# HSMC.net
KiCad netlist of a schematic drawn in Altium Designer
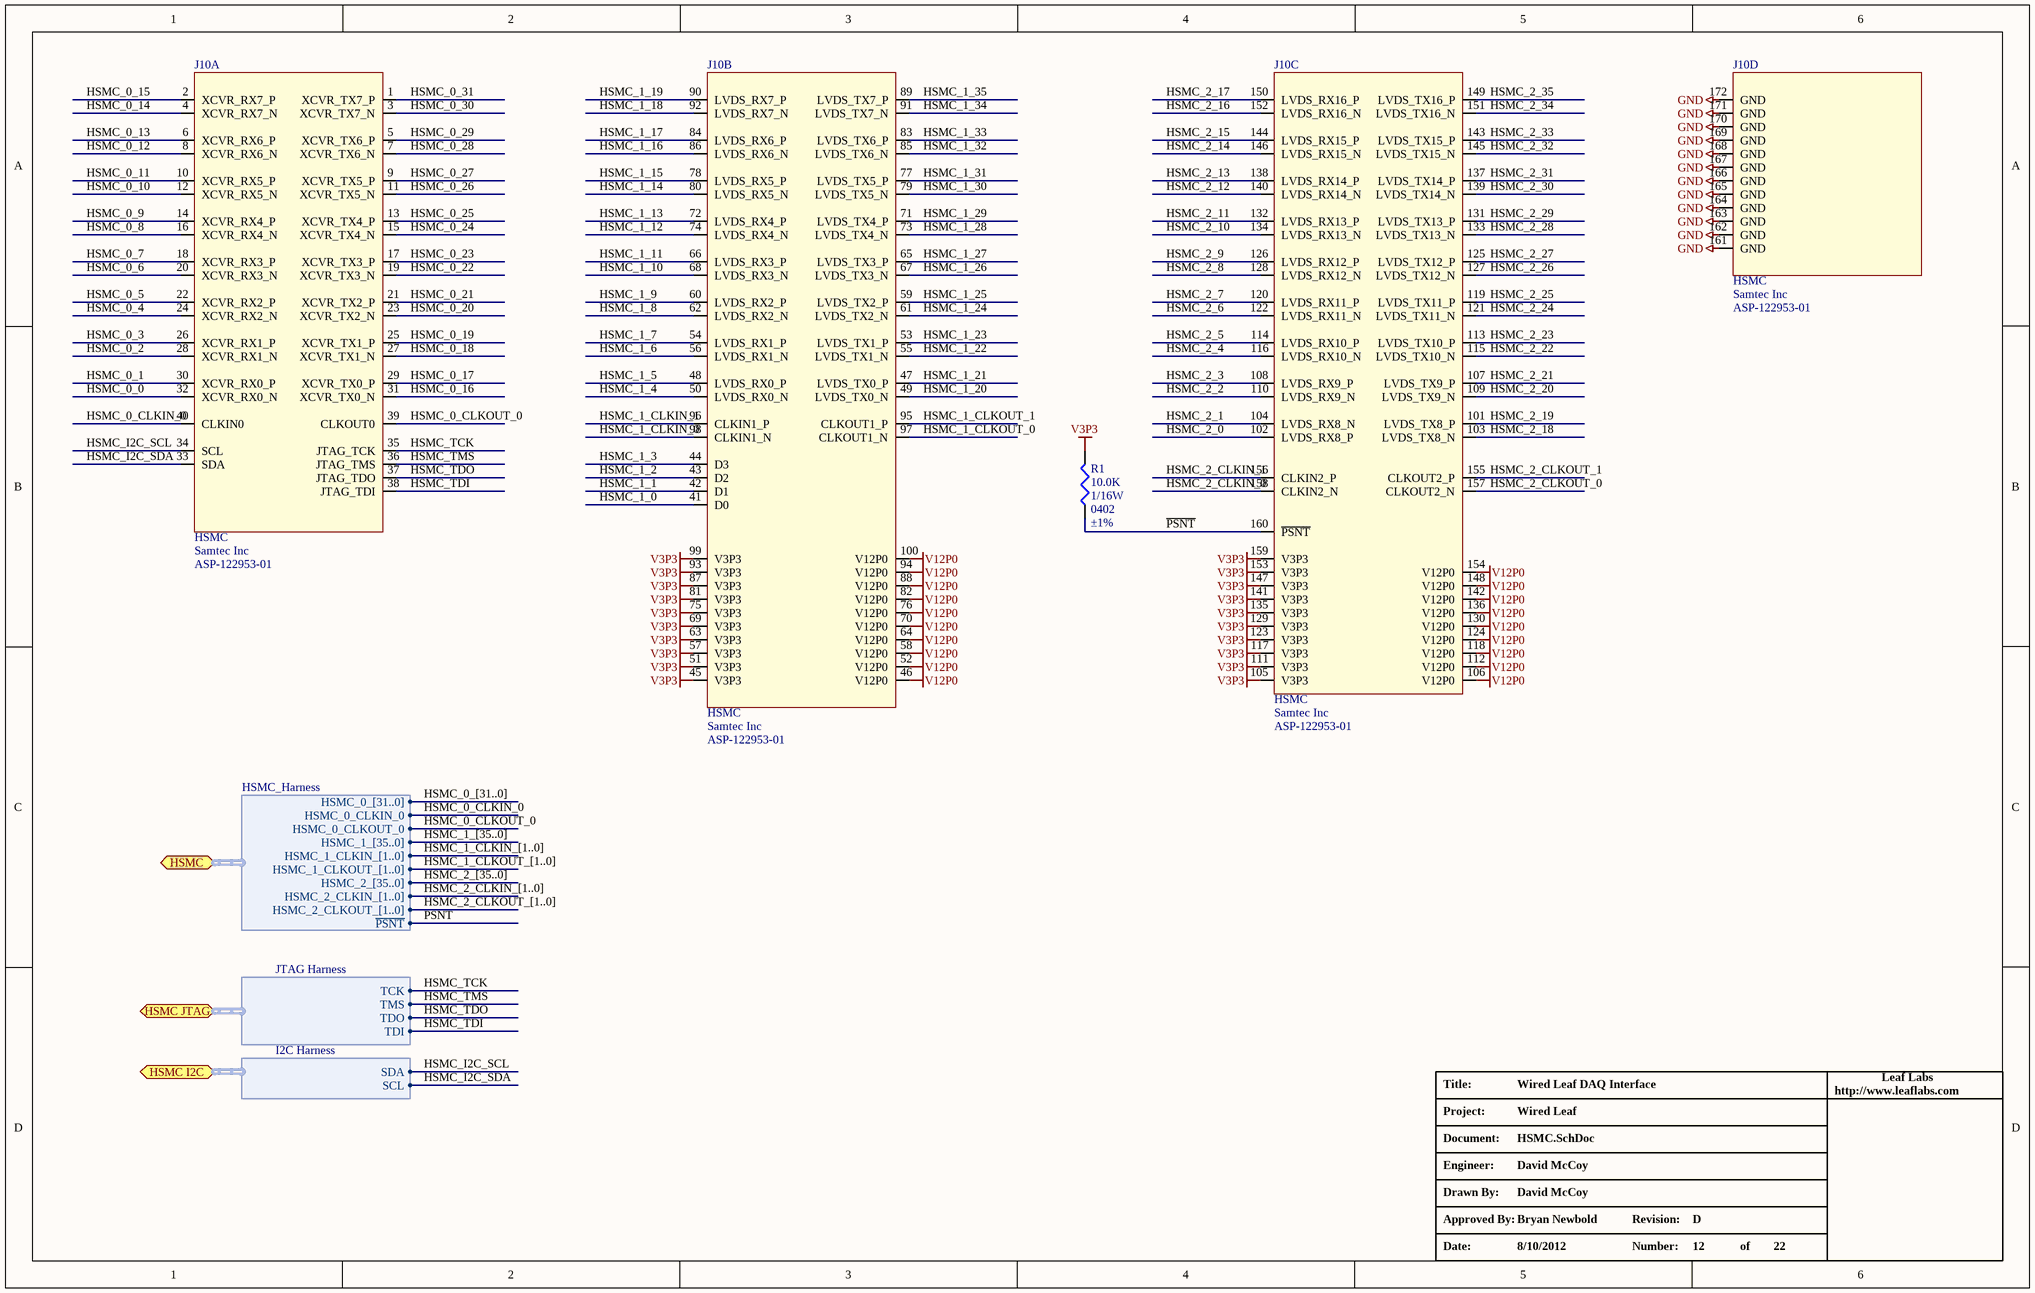
[diagram p0: HSMC.SchDoc]

(export (version "E")
  (design (tool "Eeschema 10.0.6"))
  (components
    (comp (ref "J10")
      (value "HSMC")
      (footprint "ASP-122953-01-ND")
      (description "CONN RECPT 60POS .020\" SMT GOLD")
      (fields
        (field (name "MANUFACTURER") "Samtec Inc")
        (field (name "MANUFACTURER PART NUMBER") "ASP-122953-01")
      )
      (libsource (lib "Main LibraryX") (part "J_HSMC"))
    )
    (comp (ref "R1")
      (value "R_0402_10.0K")
      (footprint "R_0402")
      (description "RES 10.0K OHM 1/16W 1% 0402 SMD")
      (fields
        (field (name "MANUFACTURER") "Vishay/Dale")
        (field (name "MANUFACTURER PART NUMBER") "CRCW040210K0FKED")
        (field (name "RESISTANCE IN OHMS") "10.0K")
        (field (name "POWER (WATTS)") "1/16W")
        (field (name "CASE") "0402")
        (field (name "TOLERANCE") "±1%")
      )
      (libsource (lib "Main Library") (part "R_0402_10.0K"))
    )
  )
  (nets
    (net (code "5") (name "/HSMC_0_0") (class "Default")
      (node (ref "J10") (pin "32") (pinfunction "XCVR_RX0_N_32") (pintype "passive"))
    )
    (net (code "6") (name "/HSMC_0_1") (class "Default")
      (node (ref "J10") (pin "30") (pinfunction "XCVR_RX0_P_30") (pintype "passive"))
    )
    (net (code "7") (name "/HSMC_0_2") (class "Default")
      (node (ref "J10") (pin "28") (pinfunction "XCVR_RX1_N_28") (pintype "passive"))
    )
    (net (code "8") (name "/HSMC_0_3") (class "Default")
      (node (ref "J10") (pin "26") (pinfunction "XCVR_RX1_P_26") (pintype "passive"))
    )
    (net (code "9") (name "/HSMC_0_4") (class "Default")
      (node (ref "J10") (pin "24") (pinfunction "XCVR_RX2_N_24") (pintype "passive"))
    )
    (net (code "10") (name "/HSMC_0_5") (class "Default")
      (node (ref "J10") (pin "22") (pinfunction "XCVR_RX2_P_22") (pintype "passive"))
    )
    (net (code "11") (name "/HSMC_0_6") (class "Default")
      (node (ref "J10") (pin "20") (pinfunction "XCVR_RX3_N_20") (pintype "passive"))
    )
    (net (code "12") (name "/HSMC_0_7") (class "Default")
      (node (ref "J10") (pin "18") (pinfunction "XCVR_RX3_P_18") (pintype "passive"))
    )
    (net (code "13") (name "/HSMC_0_8") (class "Default")
      (node (ref "J10") (pin "16") (pinfunction "XCVR_RX4_N_16") (pintype "passive"))
    )
    (net (code "14") (name "/HSMC_0_9") (class "Default")
      (node (ref "J10") (pin "14") (pinfunction "XCVR_RX4_P_14") (pintype "passive"))
    )
    (net (code "15") (name "/HSMC_0_10") (class "Default")
      (node (ref "J10") (pin "12") (pinfunction "XCVR_RX5_N_12") (pintype "passive"))
    )
    (net (code "16") (name "/HSMC_0_11") (class "Default")
      (node (ref "J10") (pin "10") (pinfunction "XCVR_RX5_P_10") (pintype "passive"))
    )
    (net (code "17") (name "/HSMC_0_12") (class "Default")
      (node (ref "J10") (pin "8") (pinfunction "XCVR_RX6_N_8") (pintype "passive"))
    )
    (net (code "18") (name "/HSMC_0_13") (class "Default")
      (node (ref "J10") (pin "6") (pinfunction "XCVR_RX6_P_6") (pintype "passive"))
    )
    (net (code "19") (name "/HSMC_0_14") (class "Default")
      (node (ref "J10") (pin "4") (pinfunction "XCVR_RX7_N_4") (pintype "passive"))
    )
    (net (code "20") (name "/HSMC_0_15") (class "Default")
      (node (ref "J10") (pin "2") (pinfunction "XCVR_RX7_P_2") (pintype "passive"))
    )
    (net (code "21") (name "/HSMC_0_16") (class "Default")
      (node (ref "J10") (pin "31") (pinfunction "XCVR_TX0_N_31") (pintype "passive"))
    )
    (net (code "22") (name "/HSMC_0_17") (class "Default")
      (node (ref "J10") (pin "29") (pinfunction "XCVR_TX0_P_29") (pintype "passive"))
    )
    (net (code "23") (name "/HSMC_0_18") (class "Default")
      (node (ref "J10") (pin "27") (pinfunction "XCVR_TX1_N_27") (pintype "passive"))
    )
    (net (code "24") (name "/HSMC_0_19") (class "Default")
      (node (ref "J10") (pin "25") (pinfunction "XCVR_TX1_P_25") (pintype "passive"))
    )
    (net (code "25") (name "/HSMC_0_20") (class "Default")
      (node (ref "J10") (pin "23") (pinfunction "XCVR_TX2_N_23") (pintype "passive"))
    )
    (net (code "26") (name "/HSMC_0_21") (class "Default")
      (node (ref "J10") (pin "21") (pinfunction "XCVR_TX2_P_21") (pintype "passive"))
    )
    (net (code "27") (name "/HSMC_0_22") (class "Default")
      (node (ref "J10") (pin "19") (pinfunction "XCVR_TX3_N_19") (pintype "passive"))
    )
    (net (code "28") (name "/HSMC_0_23") (class "Default")
      (node (ref "J10") (pin "17") (pinfunction "XCVR_TX3_P_17") (pintype "passive"))
    )
    (net (code "29") (name "/HSMC_0_24") (class "Default")
      (node (ref "J10") (pin "15") (pinfunction "XCVR_TX4_N_15") (pintype "passive"))
    )
    (net (code "30") (name "/HSMC_0_25") (class "Default")
      (node (ref "J10") (pin "13") (pinfunction "XCVR_TX4_P_13") (pintype "passive"))
    )
    (net (code "31") (name "/HSMC_0_26") (class "Default")
      (node (ref "J10") (pin "11") (pinfunction "XCVR_TX5_N_11") (pintype "passive"))
    )
    (net (code "32") (name "/HSMC_0_27") (class "Default")
      (node (ref "J10") (pin "9") (pinfunction "XCVR_TX5_P_9") (pintype "passive"))
    )
    (net (code "33") (name "/HSMC_0_28") (class "Default")
      (node (ref "J10") (pin "7") (pinfunction "XCVR_TX6_N_7") (pintype "passive"))
    )
    (net (code "34") (name "/HSMC_0_29") (class "Default")
      (node (ref "J10") (pin "5") (pinfunction "XCVR_TX6_P_5") (pintype "passive"))
    )
    (net (code "35") (name "/HSMC_0_30") (class "Default")
      (node (ref "J10") (pin "3") (pinfunction "XCVR_TX7_N_3") (pintype "passive"))
    )
    (net (code "36") (name "/HSMC_0_31") (class "Default")
      (node (ref "J10") (pin "1") (pinfunction "XCVR_TX7_P_1") (pintype "passive"))
    )
    (net (code "37") (name "/HSMC_0_CLKIN_0") (class "Default")
      (node (ref "J10") (pin "40") (pinfunction "CLKIN0_40") (pintype "passive"))
    )
    (net (code "38") (name "/HSMC_0_CLKOUT_0") (class "Default")
      (node (ref "J10") (pin "39") (pinfunction "CLKOUT0_39") (pintype "passive"))
    )
    (net (code "40") (name "/HSMC_1_0") (class "Default")
      (node (ref "J10") (pin "41") (pinfunction "D0_41") (pintype "passive"))
    )
    (net (code "41") (name "/HSMC_1_1") (class "Default")
      (node (ref "J10") (pin "42") (pinfunction "D1_42") (pintype "passive"))
    )
    (net (code "42") (name "/HSMC_1_2") (class "Default")
      (node (ref "J10") (pin "43") (pinfunction "D2_43") (pintype "passive"))
    )
    (net (code "43") (name "/HSMC_1_3") (class "Default")
      (node (ref "J10") (pin "44") (pinfunction "D3_44") (pintype "passive"))
    )
    (net (code "44") (name "/HSMC_1_4") (class "Default")
      (node (ref "J10") (pin "50") (pinfunction "LVDS_RX0_N_50") (pintype "passive"))
    )
    (net (code "45") (name "/HSMC_1_5") (class "Default")
      (node (ref "J10") (pin "48") (pinfunction "LVDS_RX0_P_48") (pintype "passive"))
    )
    (net (code "46") (name "/HSMC_1_6") (class "Default")
      (node (ref "J10") (pin "56") (pinfunction "LVDS_RX1_N_56") (pintype "passive"))
    )
    (net (code "47") (name "/HSMC_1_7") (class "Default")
      (node (ref "J10") (pin "54") (pinfunction "LVDS_RX1_P_54") (pintype "passive"))
    )
    (net (code "48") (name "/HSMC_1_8") (class "Default")
      (node (ref "J10") (pin "62") (pinfunction "LVDS_RX2_N_62") (pintype "passive"))
    )
    (net (code "49") (name "/HSMC_1_9") (class "Default")
      (node (ref "J10") (pin "60") (pinfunction "LVDS_RX2_P_60") (pintype "passive"))
    )
    (net (code "50") (name "/HSMC_1_10") (class "Default")
      (node (ref "J10") (pin "68") (pinfunction "LVDS_RX3_N_68") (pintype "passive"))
    )
    (net (code "51") (name "/HSMC_1_11") (class "Default")
      (node (ref "J10") (pin "66") (pinfunction "LVDS_RX3_P_66") (pintype "passive"))
    )
    (net (code "52") (name "/HSMC_1_12") (class "Default")
      (node (ref "J10") (pin "74") (pinfunction "LVDS_RX4_N_74") (pintype "passive"))
    )
    (net (code "53") (name "/HSMC_1_13") (class "Default")
      (node (ref "J10") (pin "72") (pinfunction "LVDS_RX4_P_72") (pintype "passive"))
    )
    (net (code "54") (name "/HSMC_1_14") (class "Default")
      (node (ref "J10") (pin "80") (pinfunction "LVDS_RX5_N_80") (pintype "passive"))
    )
    (net (code "55") (name "/HSMC_1_15") (class "Default")
      (node (ref "J10") (pin "78") (pinfunction "LVDS_RX5_P_78") (pintype "passive"))
    )
    (net (code "56") (name "/HSMC_1_16") (class "Default")
      (node (ref "J10") (pin "86") (pinfunction "LVDS_RX6_N_86") (pintype "passive"))
    )
    (net (code "57") (name "/HSMC_1_17") (class "Default")
      (node (ref "J10") (pin "84") (pinfunction "LVDS_RX6_P_84") (pintype "passive"))
    )
    (net (code "58") (name "/HSMC_1_18") (class "Default")
      (node (ref "J10") (pin "92") (pinfunction "LVDS_RX7_N_92") (pintype "passive"))
    )
    (net (code "59") (name "/HSMC_1_19") (class "Default")
      (node (ref "J10") (pin "90") (pinfunction "LVDS_RX7_P_90") (pintype "passive"))
    )
    (net (code "60") (name "/HSMC_1_20") (class "Default")
      (node (ref "J10") (pin "49") (pinfunction "LVDS_TX0_N_49") (pintype "passive"))
    )
    (net (code "61") (name "/HSMC_1_21") (class "Default")
      (node (ref "J10") (pin "47") (pinfunction "LVDS_TX0_P_47") (pintype "passive"))
    )
    (net (code "62") (name "/HSMC_1_22") (class "Default")
      (node (ref "J10") (pin "55") (pinfunction "LVDS_TX1_N_55") (pintype "passive"))
    )
    (net (code "63") (name "/HSMC_1_23") (class "Default")
      (node (ref "J10") (pin "53") (pinfunction "LVDS_TX1_P_53") (pintype "passive"))
    )
    (net (code "64") (name "/HSMC_1_24") (class "Default")
      (node (ref "J10") (pin "61") (pinfunction "LVDS_TX2_N_61") (pintype "passive"))
    )
    (net (code "65") (name "/HSMC_1_25") (class "Default")
      (node (ref "J10") (pin "59") (pinfunction "LVDS_TX2_P_59") (pintype "passive"))
    )
    (net (code "66") (name "/HSMC_1_26") (class "Default")
      (node (ref "J10") (pin "67") (pinfunction "LVDS_TX3_N_67") (pintype "passive"))
    )
    (net (code "67") (name "/HSMC_1_27") (class "Default")
      (node (ref "J10") (pin "65") (pinfunction "LVDS_TX3_P_65") (pintype "passive"))
    )
    (net (code "68") (name "/HSMC_1_28") (class "Default")
      (node (ref "J10") (pin "73") (pinfunction "LVDS_TX4_N_73") (pintype "passive"))
    )
    (net (code "69") (name "/HSMC_1_29") (class "Default")
      (node (ref "J10") (pin "71") (pinfunction "LVDS_TX4_P_71") (pintype "passive"))
    )
    (net (code "70") (name "/HSMC_1_30") (class "Default")
      (node (ref "J10") (pin "79") (pinfunction "LVDS_TX5_N_79") (pintype "passive"))
    )
    (net (code "71") (name "/HSMC_1_31") (class "Default")
      (node (ref "J10") (pin "77") (pinfunction "LVDS_TX5_P_77") (pintype "passive"))
    )
    (net (code "72") (name "/HSMC_1_32") (class "Default")
      (node (ref "J10") (pin "85") (pinfunction "LVDS_TX6_N_85") (pintype "passive"))
    )
    (net (code "73") (name "/HSMC_1_33") (class "Default")
      (node (ref "J10") (pin "83") (pinfunction "LVDS_TX6_P_83") (pintype "passive"))
    )
    (net (code "74") (name "/HSMC_1_34") (class "Default")
      (node (ref "J10") (pin "91") (pinfunction "LVDS_TX7_N_91") (pintype "passive"))
    )
    (net (code "75") (name "/HSMC_1_35") (class "Default")
      (node (ref "J10") (pin "89") (pinfunction "LVDS_TX7_P_89") (pintype "passive"))
    )
    (net (code "76") (name "/HSMC_1_CLKIN_0") (class "Default")
      (node (ref "J10") (pin "98") (pinfunction "CLKIN1_N_98") (pintype "passive"))
    )
    (net (code "77") (name "/HSMC_1_CLKIN_1") (class "Default")
      (node (ref "J10") (pin "96") (pinfunction "CLKIN1_P_96") (pintype "passive"))
    )
    (net (code "79") (name "/HSMC_1_CLKOUT_0") (class "Default")
      (node (ref "J10") (pin "97") (pinfunction "CLKOUT1_N_97") (pintype "passive"))
    )
    (net (code "80") (name "/HSMC_1_CLKOUT_1") (class "Default")
      (node (ref "J10") (pin "95") (pinfunction "CLKOUT1_P_95") (pintype "passive"))
    )
    (net (code "83") (name "/HSMC_2_0") (class "Default")
      (node (ref "J10") (pin "102") (pinfunction "LVDS_RX8_P_102") (pintype "passive"))
    )
    (net (code "84") (name "/HSMC_2_1") (class "Default")
      (node (ref "J10") (pin "104") (pinfunction "LVDS_RX8_N_104") (pintype "passive"))
    )
    (net (code "85") (name "/HSMC_2_2") (class "Default")
      (node (ref "J10") (pin "110") (pinfunction "LVDS_RX9_N_110") (pintype "passive"))
    )
    (net (code "86") (name "/HSMC_2_3") (class "Default")
      (node (ref "J10") (pin "108") (pinfunction "LVDS_RX9_P_108") (pintype "passive"))
    )
    (net (code "87") (name "/HSMC_2_4") (class "Default")
      (node (ref "J10") (pin "116") (pinfunction "LVDS_RX10_N_116") (pintype "passive"))
    )
    (net (code "88") (name "/HSMC_2_5") (class "Default")
      (node (ref "J10") (pin "114") (pinfunction "LVDS_RX10_P_114") (pintype "passive"))
    )
    (net (code "89") (name "/HSMC_2_6") (class "Default")
      (node (ref "J10") (pin "122") (pinfunction "LVDS_RX11_N_122") (pintype "passive"))
    )
    (net (code "90") (name "/HSMC_2_7") (class "Default")
      (node (ref "J10") (pin "120") (pinfunction "LVDS_RX11_P_120") (pintype "passive"))
    )
    (net (code "91") (name "/HSMC_2_8") (class "Default")
      (node (ref "J10") (pin "128") (pinfunction "LVDS_RX12_N_128") (pintype "passive"))
    )
    (net (code "92") (name "/HSMC_2_9") (class "Default")
      (node (ref "J10") (pin "126") (pinfunction "LVDS_RX12_P_126") (pintype "passive"))
    )
    (net (code "93") (name "/HSMC_2_10") (class "Default")
      (node (ref "J10") (pin "134") (pinfunction "LVDS_RX13_N_134") (pintype "passive"))
    )
    (net (code "94") (name "/HSMC_2_11") (class "Default")
      (node (ref "J10") (pin "132") (pinfunction "LVDS_RX13_P_132") (pintype "passive"))
    )
    (net (code "95") (name "/HSMC_2_12") (class "Default")
      (node (ref "J10") (pin "140") (pinfunction "LVDS_RX14_N_140") (pintype "passive"))
    )
    (net (code "96") (name "/HSMC_2_13") (class "Default")
      (node (ref "J10") (pin "138") (pinfunction "LVDS_RX14_P_138") (pintype "passive"))
    )
    (net (code "97") (name "/HSMC_2_14") (class "Default")
      (node (ref "J10") (pin "146") (pinfunction "LVDS_RX15_N_146") (pintype "passive"))
    )
    (net (code "98") (name "/HSMC_2_15") (class "Default")
      (node (ref "J10") (pin "144") (pinfunction "LVDS_RX15_P_144") (pintype "passive"))
    )
    (net (code "99") (name "/HSMC_2_16") (class "Default")
      (node (ref "J10") (pin "152") (pinfunction "LVDS_RX16_N_152") (pintype "passive"))
    )
    (net (code "100") (name "/HSMC_2_17") (class "Default")
      (node (ref "J10") (pin "150") (pinfunction "LVDS_RX16_P_150") (pintype "passive"))
    )
    (net (code "101") (name "/HSMC_2_18") (class "Default")
      (node (ref "J10") (pin "103") (pinfunction "LVDS_TX8_N_103") (pintype "passive"))
    )
    (net (code "102") (name "/HSMC_2_19") (class "Default")
      (node (ref "J10") (pin "101") (pinfunction "LVDS_TX8_P_101") (pintype "passive"))
    )
    (net (code "103") (name "/HSMC_2_20") (class "Default")
      (node (ref "J10") (pin "109") (pinfunction "LVDS_TX9_N_109") (pintype "passive"))
    )
    (net (code "104") (name "/HSMC_2_21") (class "Default")
      (node (ref "J10") (pin "107") (pinfunction "LVDS_TX9_P_107") (pintype "passive"))
    )
    (net (code "105") (name "/HSMC_2_22") (class "Default")
      (node (ref "J10") (pin "115") (pinfunction "LVDS_TX10_N_115") (pintype "passive"))
    )
    (net (code "106") (name "/HSMC_2_23") (class "Default")
      (node (ref "J10") (pin "113") (pinfunction "LVDS_TX10_P_113") (pintype "passive"))
    )
    (net (code "107") (name "/HSMC_2_24") (class "Default")
      (node (ref "J10") (pin "121") (pinfunction "LVDS_TX11_N_121") (pintype "passive"))
    )
    (net (code "108") (name "/HSMC_2_25") (class "Default")
      (node (ref "J10") (pin "119") (pinfunction "LVDS_TX11_P_119") (pintype "passive"))
    )
    (net (code "109") (name "/HSMC_2_26") (class "Default")
      (node (ref "J10") (pin "127") (pinfunction "LVDS_TX12_N_127") (pintype "passive"))
    )
    (net (code "110") (name "/HSMC_2_27") (class "Default")
      (node (ref "J10") (pin "125") (pinfunction "LVDS_TX12_P_125") (pintype "passive"))
    )
    (net (code "111") (name "/HSMC_2_28") (class "Default")
      (node (ref "J10") (pin "133") (pinfunction "LVDS_TX13_N_133") (pintype "passive"))
    )
    (net (code "112") (name "/HSMC_2_29") (class "Default")
      (node (ref "J10") (pin "131") (pinfunction "LVDS_TX13_P_131") (pintype "passive"))
    )
    (net (code "113") (name "/HSMC_2_30") (class "Default")
      (node (ref "J10") (pin "139") (pinfunction "LVDS_TX14_N_139") (pintype "passive"))
    )
    (net (code "114") (name "/HSMC_2_31") (class "Default")
      (node (ref "J10") (pin "137") (pinfunction "LVDS_TX14_P_137") (pintype "passive"))
    )
    (net (code "115") (name "/HSMC_2_32") (class "Default")
      (node (ref "J10") (pin "145") (pinfunction "LVDS_TX15_N_145") (pintype "passive"))
    )
    (net (code "116") (name "/HSMC_2_33") (class "Default")
      (node (ref "J10") (pin "143") (pinfunction "LVDS_TX15_P_143") (pintype "passive"))
    )
    (net (code "117") (name "/HSMC_2_34") (class "Default")
      (node (ref "J10") (pin "151") (pinfunction "LVDS_TX16_N_151") (pintype "passive"))
    )
    (net (code "118") (name "/HSMC_2_35") (class "Default")
      (node (ref "J10") (pin "149") (pinfunction "LVDS_TX16_P_149") (pintype "passive"))
    )
    (net (code "119") (name "/HSMC_2_CLKIN_0") (class "Default")
      (node (ref "J10") (pin "158") (pinfunction "CLKIN2_N_158") (pintype "passive"))
    )
    (net (code "120") (name "/HSMC_2_CLKIN_1") (class "Default")
      (node (ref "J10") (pin "156") (pinfunction "CLKIN2_P_156") (pintype "passive"))
    )
    (net (code "122") (name "/HSMC_2_CLKOUT_0") (class "Default")
      (node (ref "J10") (pin "157") (pinfunction "CLKOUT2_N_157") (pintype "passive"))
    )
    (net (code "123") (name "/HSMC_2_CLKOUT_1") (class "Default")
      (node (ref "J10") (pin "155") (pinfunction "CLKOUT2_P_155") (pintype "passive"))
    )
    (net (code "125") (name "/HSMC_I2C_SCL") (class "Default")
      (node (ref "J10") (pin "34") (pinfunction "SCL_34") (pintype "passive"))
    )
    (net (code "126") (name "/HSMC_I2C_SDA") (class "Default")
      (node (ref "J10") (pin "33") (pinfunction "SDA_33") (pintype "passive"))
    )
    (net (code "127") (name "/HSMC_TCK") (class "Default")
      (node (ref "J10") (pin "35") (pinfunction "JTAG_TCK_35") (pintype "passive"))
    )
    (net (code "128") (name "/HSMC_TDI") (class "Default")
      (node (ref "J10") (pin "38") (pinfunction "JTAG_TDI_38") (pintype "passive"))
    )
    (net (code "129") (name "/HSMC_TDO") (class "Default")
      (node (ref "J10") (pin "37") (pinfunction "JTAG_TDO_37") (pintype "passive"))
    )
    (net (code "130") (name "/HSMC_TMS") (class "Default")
      (node (ref "J10") (pin "36") (pinfunction "JTAG_TMS_36") (pintype "passive"))
    )
    (net (code "135") (name "/~{PSNT}") (class "Default")
      (node (ref "J10") (pin "160") (pinfunction "~{PSNT}_160") (pintype "passive"))
      (node (ref "R1") (pin "2") (pinfunction "2_2") (pintype "passive"))
    )
    (net (code "136") (name "GND") (class "Default")
      (node (ref "J10") (pin "161") (pinfunction "GND_161") (pintype "passive"))
      (node (ref "J10") (pin "162") (pinfunction "GND_162") (pintype "passive"))
      (node (ref "J10") (pin "163") (pinfunction "GND_163") (pintype "passive"))
      (node (ref "J10") (pin "164") (pinfunction "GND_164") (pintype "passive"))
      (node (ref "J10") (pin "165") (pinfunction "GND_165") (pintype "passive"))
      (node (ref "J10") (pin "166") (pinfunction "GND_166") (pintype "passive"))
      (node (ref "J10") (pin "167") (pinfunction "GND_167") (pintype "passive"))
      (node (ref "J10") (pin "168") (pinfunction "GND_168") (pintype "passive"))
      (node (ref "J10") (pin "169") (pinfunction "GND_169") (pintype "passive"))
      (node (ref "J10") (pin "170") (pinfunction "GND_170") (pintype "passive"))
      (node (ref "J10") (pin "171") (pinfunction "GND_171") (pintype "passive"))
      (node (ref "J10") (pin "172") (pinfunction "GND_172") (pintype "passive"))
    )
    (net (code "137") (name "V3P3") (class "Default")
      (node (ref "J10") (pin "105") (pinfunction "V3P3_105") (pintype "passive"))
      (node (ref "J10") (pin "111") (pinfunction "V3P3_111") (pintype "passive"))
      (node (ref "J10") (pin "117") (pinfunction "V3P3_117") (pintype "passive"))
      (node (ref "J10") (pin "123") (pinfunction "V3P3_123") (pintype "passive"))
      (node (ref "J10") (pin "129") (pinfunction "V3P3_129") (pintype "passive"))
      (node (ref "J10") (pin "135") (pinfunction "V3P3_135") (pintype "passive"))
      (node (ref "J10") (pin "141") (pinfunction "V3P3_141") (pintype "passive"))
      (node (ref "J10") (pin "147") (pinfunction "V3P3_147") (pintype "passive"))
      (node (ref "J10") (pin "153") (pinfunction "V3P3_153") (pintype "passive"))
      (node (ref "J10") (pin "159") (pinfunction "V3P3_159") (pintype "passive"))
      (node (ref "J10") (pin "45") (pinfunction "V3P3_45") (pintype "passive"))
      (node (ref "J10") (pin "51") (pinfunction "V3P3_51") (pintype "passive"))
      (node (ref "J10") (pin "57") (pinfunction "V3P3_57") (pintype "passive"))
      (node (ref "J10") (pin "63") (pinfunction "V3P3_63") (pintype "passive"))
      (node (ref "J10") (pin "69") (pinfunction "V3P3_69") (pintype "passive"))
      (node (ref "J10") (pin "75") (pinfunction "V3P3_75") (pintype "passive"))
      (node (ref "J10") (pin "81") (pinfunction "V3P3_81") (pintype "passive"))
      (node (ref "J10") (pin "87") (pinfunction "V3P3_87") (pintype "passive"))
      (node (ref "J10") (pin "93") (pinfunction "V3P3_93") (pintype "passive"))
      (node (ref "J10") (pin "99") (pinfunction "V3P3_99") (pintype "passive"))
      (node (ref "R1") (pin "1") (pinfunction "1_1") (pintype "passive"))
    )
    (net (code "138") (name "V12P0") (class "Default")
      (node (ref "J10") (pin "100") (pinfunction "V12P0_100") (pintype "passive"))
      (node (ref "J10") (pin "106") (pinfunction "V12P0_106") (pintype "passive"))
      (node (ref "J10") (pin "112") (pinfunction "V12P0_112") (pintype "passive"))
      (node (ref "J10") (pin "118") (pinfunction "V12P0_118") (pintype "passive"))
      (node (ref "J10") (pin "124") (pinfunction "V12P0_124") (pintype "passive"))
      (node (ref "J10") (pin "130") (pinfunction "V12P0_130") (pintype "passive"))
      (node (ref "J10") (pin "136") (pinfunction "V12P0_136") (pintype "passive"))
      (node (ref "J10") (pin "142") (pinfunction "V12P0_142") (pintype "passive"))
      (node (ref "J10") (pin "148") (pinfunction "V12P0_148") (pintype "passive"))
      (node (ref "J10") (pin "154") (pinfunction "V12P0_154") (pintype "passive"))
      (node (ref "J10") (pin "46") (pinfunction "V12P0_46") (pintype "passive"))
      (node (ref "J10") (pin "52") (pinfunction "V12P0_52") (pintype "passive"))
      (node (ref "J10") (pin "58") (pinfunction "V12P0_58") (pintype "passive"))
      (node (ref "J10") (pin "64") (pinfunction "V12P0_64") (pintype "passive"))
      (node (ref "J10") (pin "70") (pinfunction "V12P0_70") (pintype "passive"))
      (node (ref "J10") (pin "76") (pinfunction "V12P0_76") (pintype "passive"))
      (node (ref "J10") (pin "82") (pinfunction "V12P0_82") (pintype "passive"))
      (node (ref "J10") (pin "88") (pinfunction "V12P0_88") (pintype "passive"))
      (node (ref "J10") (pin "94") (pinfunction "V12P0_94") (pintype "passive"))
    )
  )
)
